# untitled.net
KiCad netlist of a schematic drawn in EAGLE
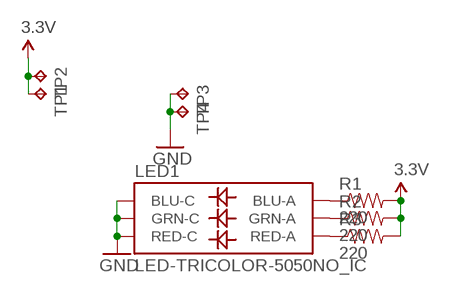
[diagram p0: schematic, sheet 1]

(export (version "E")
  (design (tool "Eeschema 10.0.6"))
  (components
    (comp (ref "LED1")
      (value "LED-TRICOLOR-5050NO_IC")
      (footprint "eagle-import:LED-TRICOLOR-5050")
      (libsource (lib "eagle-import") (part "LED-TRICOLOR-5050NO_IC"))
    )
    (comp (ref "R1")
      (value "220")
      (footprint "eagle-import:0603-RES")
      (libsource (lib "eagle-import") (part "220OHM-1/10W-1%(0603)"))
    )
    (comp (ref "R2")
      (value "220")
      (footprint "eagle-import:0603-RES")
      (libsource (lib "eagle-import") (part "220OHM-1/10W-1%(0603)"))
    )
    (comp (ref "R3")
      (value "220")
      (footprint "eagle-import:0603-RES")
      (libsource (lib "eagle-import") (part "220OHM-1/10W-1%(0603)"))
    )
    (comp (ref "TP1")
      (value "TPTP15SQ")
      (footprint "eagle-import:TP15SQ")
      (libsource (lib "eagle-import") (part "TPTP15SQ"))
    )
    (comp (ref "TP2")
      (value "TPTP15SQ")
      (footprint "eagle-import:TP15SQ")
      (libsource (lib "eagle-import") (part "TPTP15SQ"))
    )
    (comp (ref "TP3")
      (value "TPTP15SQ")
      (footprint "eagle-import:TP15SQ")
      (libsource (lib "eagle-import") (part "TPTP15SQ"))
    )
    (comp (ref "TP4")
      (value "TPTP15SQ")
      (footprint "eagle-import:TP15SQ")
      (libsource (lib "eagle-import") (part "TPTP15SQ"))
    )
  )
  (nets
    (net (code "1") (name "3.3V") (class "Default")
      (node (ref "R1") (pin "2") (pinfunction "2_2") (pintype "passive"))
      (node (ref "R2") (pin "2") (pinfunction "2_2") (pintype "passive"))
      (node (ref "R3") (pin "2") (pinfunction "2_2") (pintype "passive"))
      (node (ref "TP1") (pin "TP") (pinfunction "TP_TP") (pintype "input"))
      (node (ref "TP2") (pin "TP") (pinfunction "TP_TP") (pintype "input"))
    )
    (net (code "2") (name "GND") (class "Default")
      (node (ref "LED1") (pin "4") (pinfunction "BLU-C_4") (pintype "bidirectional"))
      (node (ref "LED1") (pin "5") (pinfunction "RED-C_5") (pintype "bidirectional"))
      (node (ref "LED1") (pin "6") (pinfunction "GRN-C_6") (pintype "bidirectional"))
      (node (ref "TP3") (pin "TP") (pinfunction "TP_TP") (pintype "input"))
      (node (ref "TP4") (pin "TP") (pinfunction "TP_TP") (pintype "input"))
    )
    (net (code "3") (name "Net-(LED1-BLU-A)") (class "Default")
      (node (ref "LED1") (pin "3") (pinfunction "BLU-A_3") (pintype "bidirectional"))
      (node (ref "R1") (pin "1") (pinfunction "1_1") (pintype "passive"))
    )
    (net (code "4") (name "Net-(LED1-GRN-A)") (class "Default")
      (node (ref "LED1") (pin "1") (pinfunction "GRN-A_1") (pintype "bidirectional"))
      (node (ref "R2") (pin "1") (pinfunction "1_1") (pintype "passive"))
    )
    (net (code "5") (name "Net-(LED1-RED-A)") (class "Default")
      (node (ref "LED1") (pin "2") (pinfunction "RED-A_2") (pintype "bidirectional"))
      (node (ref "R3") (pin "1") (pinfunction "1_1") (pintype "passive"))
    )
  )
)
